# GPS_dev_board.net
KiCad netlist of a schematic drawn in EAGLE
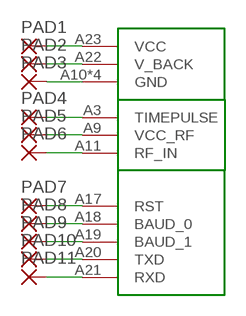
[diagram p0: schematic, sheet 1]

(export (version "E")
  (design (tool "Eeschema 10.0.6"))
  (components
    (comp (ref "PAD1")
      (value "2,54/0,8")
      (footprint "eagle-import:2,54_0,8")
      (libsource (lib "eagle-import") (part "2,54/0,8"))
    )
    (comp (ref "PAD2")
      (value "2,54/0,8")
      (footprint "eagle-import:2,54_0,8")
      (libsource (lib "eagle-import") (part "2,54/0,8"))
    )
    (comp (ref "PAD3")
      (value "2,54/0,8")
      (footprint "eagle-import:2,54_0,8")
      (libsource (lib "eagle-import") (part "2,54/0,8"))
    )
    (comp (ref "PAD4")
      (value "2,54/0,8")
      (footprint "eagle-import:2,54_0,8")
      (libsource (lib "eagle-import") (part "2,54/0,8"))
    )
    (comp (ref "PAD5")
      (value "2,54/0,8")
      (footprint "eagle-import:2,54_0,8")
      (libsource (lib "eagle-import") (part "2,54/0,8"))
    )
    (comp (ref "PAD6")
      (value "2,54/0,8")
      (footprint "eagle-import:2,54_0,8")
      (libsource (lib "eagle-import") (part "2,54/0,8"))
    )
    (comp (ref "PAD7")
      (value "2,54/0,8")
      (footprint "eagle-import:2,54_0,8")
      (libsource (lib "eagle-import") (part "2,54/0,8"))
    )
    (comp (ref "PAD8")
      (value "2,54/0,8")
      (footprint "eagle-import:2,54_0,8")
      (libsource (lib "eagle-import") (part "2,54/0,8"))
    )
    (comp (ref "PAD9")
      (value "2,54/0,8")
      (footprint "eagle-import:2,54_0,8")
      (libsource (lib "eagle-import") (part "2,54/0,8"))
    )
    (comp (ref "PAD10")
      (value "2,54/0,8")
      (footprint "eagle-import:2,54_0,8")
      (libsource (lib "eagle-import") (part "2,54/0,8"))
    )
    (comp (ref "PAD11")
      (value "2,54/0,8")
      (footprint "eagle-import:2,54_0,8")
      (libsource (lib "eagle-import") (part "2,54/0,8"))
    )
    (comp (ref "U$1")
      (value "GTS-4E-60")
      (footprint "eagle-import:GTS-4E-60")
      (libsource (lib "eagle-import") (part "GTS-4E-60"))
    )
  )
  (nets
    (net (code "1") (name "Net-(PAD1-P)") (class "Default")
      (node (ref "PAD1") (pin "1") (pinfunction "P_1") (pintype "passive"))
      (node (ref "U$1") (pin "A23") (pinfunction "VCC_A23") (pintype "bidirectional"))
    )
    (net (code "2") (name "Net-(PAD2-P)") (class "Default")
      (node (ref "PAD2") (pin "1") (pinfunction "P_1") (pintype "passive"))
      (node (ref "U$1") (pin "A22") (pinfunction "V_BACK_A22") (pintype "bidirectional"))
    )
    (net (code "3") (name "Net-(PAD3-P)") (class "Default")
      (node (ref "PAD3") (pin "1") (pinfunction "P_1") (pintype "passive"))
      (node (ref "U$1") (pin "A10") (pinfunction "GND_A10") (pintype "bidirectional"))
      (node (ref "U$1") (pin "A12") (pinfunction "GND_A12") (pintype "bidirectional"))
      (node (ref "U$1") (pin "A13") (pinfunction "GND_A13") (pintype "bidirectional"))
      (node (ref "U$1") (pin "A24") (pinfunction "GND_A24") (pintype "bidirectional"))
    )
    (net (code "4") (name "Net-(PAD4-P)") (class "Default")
      (node (ref "PAD4") (pin "1") (pinfunction "P_1") (pintype "passive"))
      (node (ref "U$1") (pin "A3") (pinfunction "TIMEPULSE_A3") (pintype "bidirectional"))
    )
    (net (code "5") (name "Net-(PAD5-P)") (class "Default")
      (node (ref "PAD5") (pin "1") (pinfunction "P_1") (pintype "passive"))
      (node (ref "U$1") (pin "A9") (pinfunction "VCC_RF_A9") (pintype "bidirectional"))
    )
    (net (code "6") (name "Net-(PAD6-P)") (class "Default")
      (node (ref "PAD6") (pin "1") (pinfunction "P_1") (pintype "passive"))
      (node (ref "U$1") (pin "A11") (pinfunction "RF_IN_A11") (pintype "bidirectional"))
    )
    (net (code "7") (name "Net-(PAD7-P)") (class "Default")
      (node (ref "PAD7") (pin "1") (pinfunction "P_1") (pintype "passive"))
      (node (ref "U$1") (pin "A17") (pinfunction "RST_A17") (pintype "bidirectional"))
    )
    (net (code "8") (name "Net-(PAD8-P)") (class "Default")
      (node (ref "PAD8") (pin "1") (pinfunction "P_1") (pintype "passive"))
      (node (ref "U$1") (pin "A18") (pinfunction "BAUD_0_A18") (pintype "bidirectional"))
    )
    (net (code "9") (name "Net-(PAD9-P)") (class "Default")
      (node (ref "PAD9") (pin "1") (pinfunction "P_1") (pintype "passive"))
      (node (ref "U$1") (pin "A19") (pinfunction "BAUD_1_A19") (pintype "bidirectional"))
    )
    (net (code "10") (name "Net-(PAD10-P)") (class "Default")
      (node (ref "PAD10") (pin "1") (pinfunction "P_1") (pintype "passive"))
      (node (ref "U$1") (pin "A20") (pinfunction "TXD_A20") (pintype "bidirectional"))
    )
    (net (code "11") (name "Net-(PAD11-P)") (class "Default")
      (node (ref "PAD11") (pin "1") (pinfunction "P_1") (pintype "passive"))
      (node (ref "U$1") (pin "A21") (pinfunction "RXD_A21") (pintype "bidirectional"))
    )
  )
)
